# thermocouple.net
KiCad netlist of a schematic drawn in EAGLE
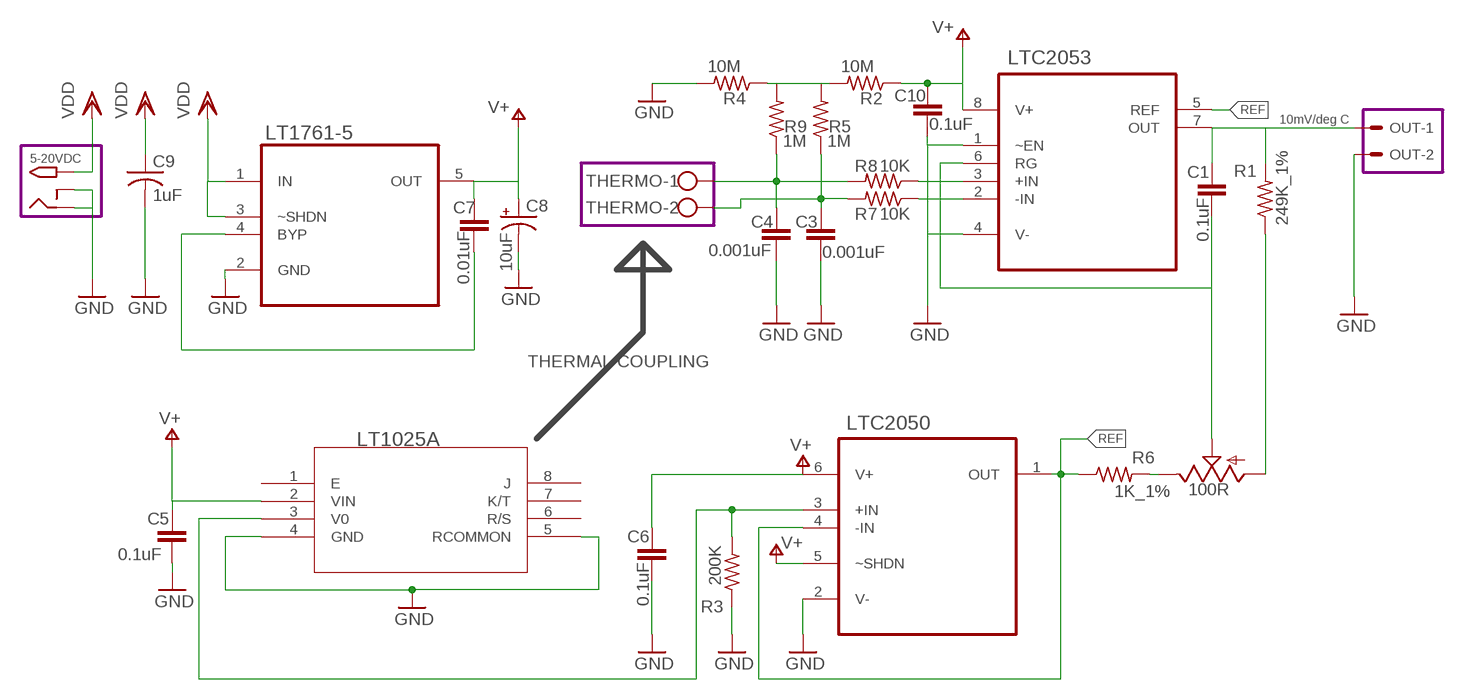
[diagram p0: schematic, sheet 1]

(export (version "E")
  (design (tool "Eeschema 10.0.6"))
  (components
    (comp (ref "5-20VDC")
      (value "DC_IN")
      (footprint "eagle-import:PJ-102A")
      (libsource (lib "eagle-import") (part "2.1MMJACKTHM"))
    )
    (comp (ref "C1")
      (value "0.1uF")
      (footprint "eagle-import:C0805")
      (libsource (lib "eagle-import") (part "C-EUC0805"))
    )
    (comp (ref "C3")
      (value "0.001uF")
      (footprint "eagle-import:C0805")
      (libsource (lib "eagle-import") (part "C-EUC0805"))
    )
    (comp (ref "C4")
      (value "0.001uF")
      (footprint "eagle-import:C0805")
      (libsource (lib "eagle-import") (part "C-EUC0805"))
    )
    (comp (ref "C5")
      (value "0.1uF")
      (footprint "eagle-import:C0805")
      (libsource (lib "eagle-import") (part "C-EUC0805"))
    )
    (comp (ref "C6")
      (value "0.1uF")
      (footprint "eagle-import:C0805")
      (libsource (lib "eagle-import") (part "C-EUC0805"))
    )
    (comp (ref "C7")
      (value "0.01uF")
      (footprint "eagle-import:C0805")
      (libsource (lib "eagle-import") (part "C-EUC0805"))
    )
    (comp (ref "C8")
      (value "10uF")
      (footprint "eagle-import:E2,5-6E")
      (libsource (lib "eagle-import") (part "CPOL-USE2,5-6E"))
    )
    (comp (ref "C9")
      (value "1uF")
      (footprint "eagle-import:C0805")
      (libsource (lib "eagle-import") (part "C-USC0805"))
    )
    (comp (ref "C10")
      (value "0.1uF")
      (footprint "eagle-import:C0805")
      (libsource (lib "eagle-import") (part "C-EUC0805"))
    )
    (comp (ref "OUT")
      (value "10mV/C")
      (footprint "eagle-import:6410-02")
      (libsource (lib "eagle-import") (part "22-?-0227-2021"))
    )
    (comp (ref "POT")
      (value "100R")
      (footprint "eagle-import:6MM")
      (libsource (lib "eagle-import") (part "TRIM"))
    )
    (comp (ref "R1")
      (value "249K_1%")
      (footprint "eagle-import:R0805")
      (libsource (lib "eagle-import") (part "R-US_R0805"))
    )
    (comp (ref "R2")
      (value "10M")
      (footprint "eagle-import:R0805")
      (libsource (lib "eagle-import") (part "R-US_R0805"))
    )
    (comp (ref "R3")
      (value "200K")
      (footprint "eagle-import:M0805")
      (libsource (lib "eagle-import") (part "R-US_M0805"))
    )
    (comp (ref "R4")
      (value "10M")
      (footprint "eagle-import:R0805")
      (libsource (lib "eagle-import") (part "R-US_R0805"))
    )
    (comp (ref "R5")
      (value "1M")
      (footprint "eagle-import:R0805")
      (libsource (lib "eagle-import") (part "R-US_R0805"))
    )
    (comp (ref "R6")
      (value "1K_1%")
      (footprint "eagle-import:R0805")
      (libsource (lib "eagle-import") (part "R-US_R0805"))
    )
    (comp (ref "R7")
      (value "10K")
      (footprint "eagle-import:R0805")
      (libsource (lib "eagle-import") (part "R-US_R0805"))
    )
    (comp (ref "R8")
      (value "10K")
      (footprint "eagle-import:R0805")
      (libsource (lib "eagle-import") (part "R-US_R0805"))
    )
    (comp (ref "R9")
      (value "1M")
      (footprint "eagle-import:R0805")
      (libsource (lib "eagle-import") (part "R-US_R0805"))
    )
    (comp (ref "THERMO")
      (value "W237-102")
      (footprint "eagle-import:W237-102")
      (fields (field (name "MPN") "237-102"))
      (libsource (lib "eagle-import") (part "W237-102"))
    )
    (comp (ref "U1")
      (value "LT1025A")
      (footprint "eagle-import:PDIP-8_N")
      (fields (field (name "MF") "Linear Technology") (field (name "MP") "LT1025ACN8"))
      (libsource (lib "eagle-import") (part "LT1025ACN8"))
    )
    (comp (ref "U2")
      (value "LTC2053")
      (footprint "eagle-import:SOP65P490X110-8N")
      (fields (field (name "MPN") "LTC2053CMS8#PBF"))
      (libsource (lib "eagle-import") (part "LTC2053CMS8PBF"))
    )
    (comp (ref "U3")
      (value "LTC2050")
      (footprint "eagle-import:SOT95P280X100-6N")
      (fields (field (name "MPN") "LTC2050HVIS6#PBF"))
      (libsource (lib "eagle-import") (part "LTC2050HVIS6PBF"))
    )
    (comp (ref "U4")
      (value "LT1761-5")
      (footprint "eagle-import:SOT95P280X100-5N")
      (fields (field (name "MPN") "LT1761ES5-5#PBF"))
      (libsource (lib "eagle-import") (part "LT1761ES5-5PBF"))
    )
  )
  (nets
    (net (code "1") (name "GND") (class "Default")
      (node (ref "5-20VDC") (pin "RING") (pinfunction "RING_RING") (pintype "bidirectional"))
      (node (ref "5-20VDC") (pin "RING_SW") (pinfunction "RING_SW_RING_SW") (pintype "bidirectional"))
      (node (ref "C10") (pin "1") (pinfunction "1_1") (pintype "passive"))
      (node (ref "C3") (pin "1") (pinfunction "1_1") (pintype "passive"))
      (node (ref "C4") (pin "2") (pinfunction "2_2") (pintype "passive"))
      (node (ref "C5") (pin "2") (pinfunction "2_2") (pintype "passive"))
      (node (ref "C6") (pin "2") (pinfunction "2_2") (pintype "passive"))
      (node (ref "C8") (pin "-") (pinfunction "-_-") (pintype "passive"))
      (node (ref "C9") (pin "2") (pinfunction "2_2") (pintype "passive"))
      (node (ref "OUT") (pin "2") (pinfunction "S_2") (pintype "passive"))
      (node (ref "R3") (pin "1") (pinfunction "1_1") (pintype "passive"))
      (node (ref "R4") (pin "2") (pinfunction "2_2") (pintype "passive"))
      (node (ref "U1") (pin "4") (pinfunction "GND_4") (pintype "power_in"))
      (node (ref "U1") (pin "5") (pinfunction "RCOMMON_5") (pintype "passive"))
      (node (ref "U2") (pin "1") (pinfunction "~{EN}_1") (pintype "input"))
      (node (ref "U2") (pin "4") (pinfunction "V-_4") (pintype "power_in"))
      (node (ref "U3") (pin "2") (pinfunction "V-_2") (pintype "power_in"))
      (node (ref "U4") (pin "2") (pinfunction "GND_2") (pintype "passive"))
    )
    (net (code "2") (name "Net-(OUTA-S)") (class "Default")
      (node (ref "C1") (pin "1") (pinfunction "1_1") (pintype "passive"))
      (node (ref "OUT") (pin "1") (pinfunction "S_1") (pintype "passive"))
      (node (ref "R1") (pin "2") (pinfunction "2_2") (pintype "passive"))
      (node (ref "U2") (pin "7") (pinfunction "OUT_7") (pintype "output"))
    )
    (net (code "3") (name "Net-(POT-PadA)") (class "Default")
      (node (ref "POT") (pin "A") (pinfunction "A_A") (pintype "passive"))
      (node (ref "R1") (pin "1") (pinfunction "1_1") (pintype "passive"))
    )
    (net (code "4") (name "Net-(POT-PadE)") (class "Default")
      (node (ref "POT") (pin "E") (pinfunction "E_E") (pintype "passive"))
      (node (ref "R6") (pin "2") (pinfunction "2_2") (pintype "passive"))
    )
    (net (code "5") (name "Net-(R2-Pad2)") (class "Default")
      (node (ref "R2") (pin "2") (pinfunction "2_2") (pintype "passive"))
      (node (ref "R4") (pin "1") (pinfunction "1_1") (pintype "passive"))
      (node (ref "R5") (pin "2") (pinfunction "2_2") (pintype "passive"))
      (node (ref "R9") (pin "2") (pinfunction "2_2") (pintype "passive"))
    )
    (net (code "6") (name "Net-(THERMOA-KL)") (class "Default")
      (node (ref "C4") (pin "1") (pinfunction "1_1") (pintype "passive"))
      (node (ref "R8") (pin "2") (pinfunction "2_2") (pintype "passive"))
      (node (ref "R9") (pin "1") (pinfunction "1_1") (pintype "passive"))
      (node (ref "THERMO") (pin "1") (pinfunction "KL_1") (pintype "passive"))
    )
    (net (code "7") (name "Net-(THERMOB-KL)") (class "Default")
      (node (ref "C3") (pin "2") (pinfunction "2_2") (pintype "passive"))
      (node (ref "R5") (pin "1") (pinfunction "1_1") (pintype "passive"))
      (node (ref "R7") (pin "2") (pinfunction "2_2") (pintype "passive"))
      (node (ref "THERMO") (pin "2") (pinfunction "KL_2") (pintype "passive"))
    )
    (net (code "8") (name "Net-(U1-V0)") (class "Default")
      (node (ref "R3") (pin "2") (pinfunction "2_2") (pintype "passive"))
      (node (ref "U1") (pin "3") (pinfunction "V0_3") (pintype "power_in"))
      (node (ref "U3") (pin "3") (pinfunction "+IN_3") (pintype "input"))
    )
    (net (code "9") (name "Net-(U2-+IN)") (class "Default")
      (node (ref "R8") (pin "1") (pinfunction "1_1") (pintype "passive"))
      (node (ref "U2") (pin "3") (pinfunction "+IN_3") (pintype "input"))
    )
    (net (code "10") (name "Net-(U2--IN)") (class "Default")
      (node (ref "R7") (pin "1") (pinfunction "1_1") (pintype "passive"))
      (node (ref "U2") (pin "2") (pinfunction "-IN_2") (pintype "input"))
    )
    (net (code "11") (name "Net-(U2-RG)") (class "Default")
      (node (ref "C1") (pin "2") (pinfunction "2_2") (pintype "passive"))
      (node (ref "POT") (pin "S") (pinfunction "S_S") (pintype "passive"))
      (node (ref "U2") (pin "6") (pinfunction "RG_6") (pintype "input"))
    )
    (net (code "12") (name "Net-(U4-BYP)") (class "Default")
      (node (ref "C7") (pin "2") (pinfunction "2_2") (pintype "passive"))
      (node (ref "U4") (pin "4") (pinfunction "BYP_4") (pintype "passive"))
    )
    (net (code "13") (name "REF") (class "Default")
      (node (ref "R6") (pin "1") (pinfunction "1_1") (pintype "passive"))
      (node (ref "U2") (pin "5") (pinfunction "REF_5") (pintype "output"))
      (node (ref "U3") (pin "1") (pinfunction "OUT_1") (pintype "output"))
      (node (ref "U3") (pin "4") (pinfunction "-IN_4") (pintype "input"))
    )
    (net (code "14") (name "V+") (class "Default")
      (node (ref "C10") (pin "2") (pinfunction "2_2") (pintype "passive"))
      (node (ref "C5") (pin "1") (pinfunction "1_1") (pintype "passive"))
      (node (ref "C6") (pin "1") (pinfunction "1_1") (pintype "passive"))
      (node (ref "C7") (pin "1") (pinfunction "1_1") (pintype "passive"))
      (node (ref "C8") (pin "+") (pinfunction "+_+") (pintype "passive"))
      (node (ref "R2") (pin "1") (pinfunction "1_1") (pintype "passive"))
      (node (ref "U1") (pin "2") (pinfunction "VIN_2") (pintype "power_in"))
      (node (ref "U2") (pin "8") (pinfunction "V+_8") (pintype "power_in"))
      (node (ref "U3") (pin "5") (pinfunction "~{SHDN}_5") (pintype "input"))
      (node (ref "U3") (pin "6") (pinfunction "V+_6") (pintype "power_in"))
      (node (ref "U4") (pin "5") (pinfunction "OUT_5") (pintype "output"))
    )
    (net (code "15") (name "VDD") (class "Default")
      (node (ref "5-20VDC") (pin "TIP") (pinfunction "TIP_TIP") (pintype "bidirectional"))
      (node (ref "C9") (pin "1") (pinfunction "1_1") (pintype "passive"))
      (node (ref "U4") (pin "1") (pinfunction "IN_1") (pintype "input"))
      (node (ref "U4") (pin "3") (pinfunction "~{SHDN}_3") (pintype "input"))
    )
    (net (code "16") (name "unconnected-(U1-E-Pad1)") (class "Default")
      (node (ref "U1") (pin "1") (pinfunction "E_1") (pintype "passive"))
    )
    (net (code "17") (name "unconnected-(U1-J-Pad8)") (class "Default")
      (node (ref "U1") (pin "8") (pinfunction "J_8") (pintype "passive"))
    )
    (net (code "18") (name "unconnected-(U1-K{slash}T-Pad7)") (class "Default")
      (node (ref "U1") (pin "7") (pinfunction "K/T_7") (pintype "passive"))
    )
    (net (code "19") (name "unconnected-(U1-R{slash}S-Pad6)") (class "Default")
      (node (ref "U1") (pin "6") (pinfunction "R/S_6") (pintype "passive"))
    )
  )
)
